# EndEffector-_Power.net
KiCad netlist of a schematic drawn in Altium Designer
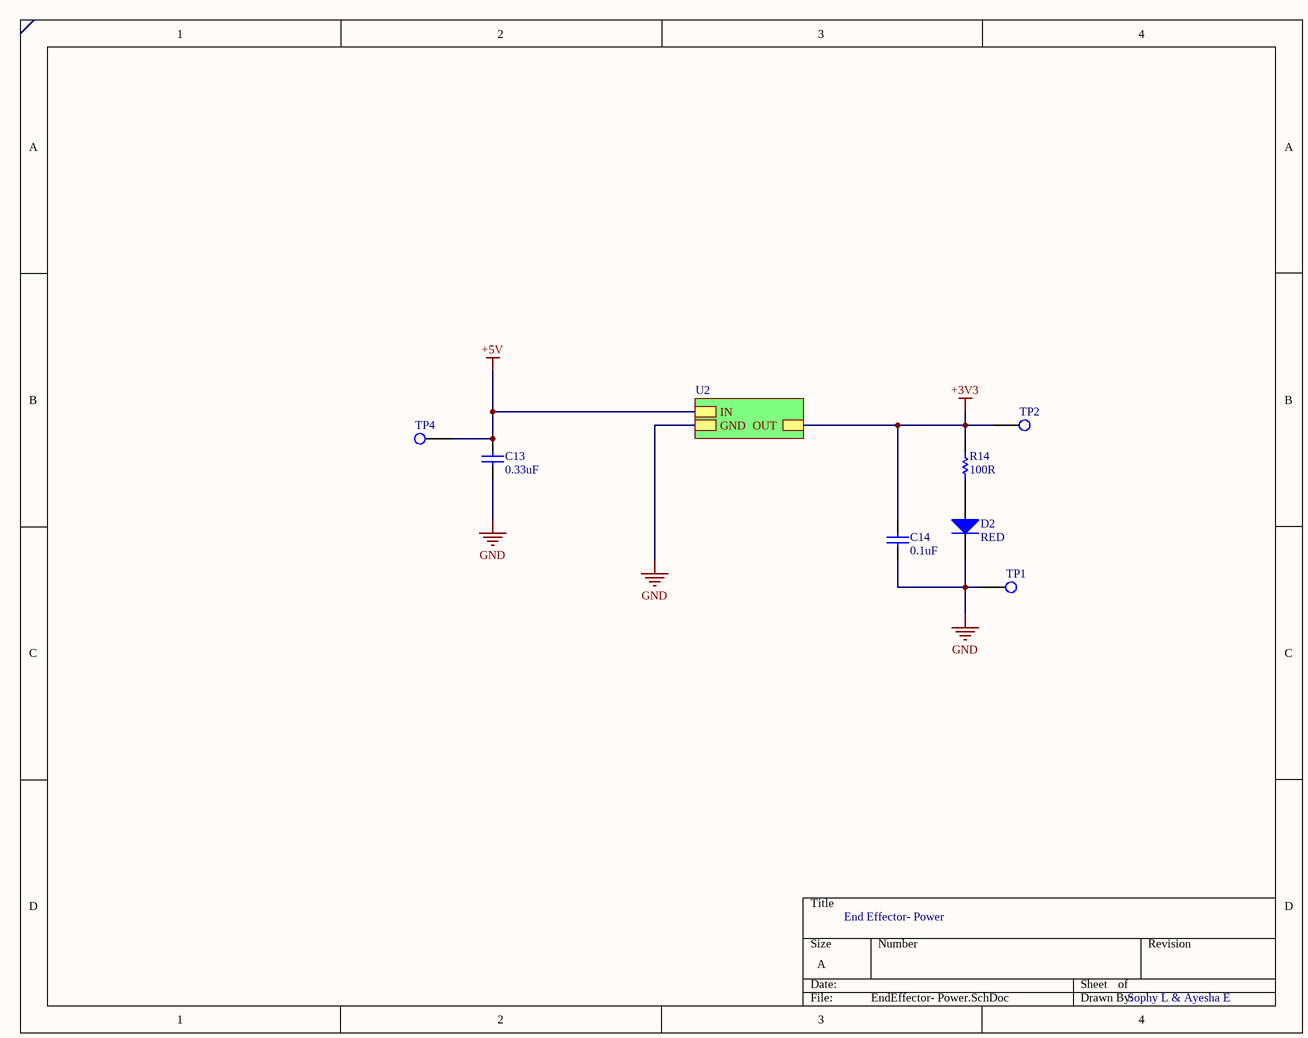
[diagram p0: EndEffector- Power.SchDoc]

(export (version "E")
  (design (tool "Eeschema 10.0.6"))
  (components
    (comp (ref "C13")
      (value "0.33uF")
      (footprint "CAPC0603(1608)55_N")
      (description "CAP CER 0.1UF 16V X7R 0603")
      (fields (field (name "PART NUMBER") "CC0603KRX7R7BB104") (field (name "MANUFACTURER") "Yageo"))
      (libsource (lib "UWRT_Schematic_Library_2019") (part "CAP_0.1uF_16V_0603"))
    )
    (comp (ref "C14")
      (value "0.1uF")
      (footprint "CAPC0603(1608)55_N")
      (description "CAP CER 0.1UF 16V X7R 0603")
      (fields (field (name "PART NUMBER") "CC0603KRX7R7BB104") (field (name "MANUFACTURER") "Yageo"))
      (libsource (lib "UWRT_Schematic_Library_2019") (part "CAP_0.1uF_16V_0603"))
    )
    (comp (ref "D2")
      (value "RED")
      (footprint "LED-1")
      (description "ESD PROTECTION DIODE")
      (fields (field (name "PART NUMBER") "BAS16GW") (field (name "MANUFACTURER") "Nexperia"))
      (libsource (lib "UWRT_Schematic_Library_2019") (part "DIO_BAS16GW"))
    )
    (comp (ref "R14")
      (value "100R")
      (footprint "RESC0201(0603)_N")
      (description "RES SMD 120 OHM 5% 1/10W 0603")
      (fields (field (name "MANUFACTURER") "Yageo") (field (name "TOLERANCE") "5%"))
      (libsource (lib "UWRT_Schematic_Library_2019") (part "RES_120R_0603"))
    )
    (comp (ref "TP1")
      (value "~")
      (footprint "TESTPOINT_LOOP")
      (libsource (lib "UWRT_Schematic_Library_2019") (part "TESTPOINT_LOOP"))
    )
    (comp (ref "TP2")
      (value "~")
      (footprint "TESTPOINT_LOOP")
      (libsource (lib "UWRT_Schematic_Library_2019") (part "TESTPOINT_LOOP"))
    )
    (comp (ref "TP4")
      (value "~")
      (footprint "TESTPOINT_LOOP")
      (libsource (lib "UWRT_Schematic_Library_2019") (part "TESTPOINT_LOOP"))
    )
  )
  (nets
    (net (code "1") (name "+3V3") (class "Default")
      (node (ref "C14") (pin "2") (pinfunction "2_2") (pintype "passive"))
      (node (ref "R14") (pin "2") (pinfunction "2_2") (pintype "passive"))
      (node (ref "TP2") (pin "1") (pinfunction "=value_1") (pintype "passive"))
    )
    (net (code "2") (name "+5V") (class "Default")
      (node (ref "C13") (pin "2") (pinfunction "2_2") (pintype "passive"))
      (node (ref "TP4") (pin "1") (pinfunction "=value_1") (pintype "passive"))
    )
    (net (code "3") (name "GND") (class "Default")
      (node (ref "C13") (pin "1") (pinfunction "1_1") (pintype "passive"))
      (node (ref "C14") (pin "1") (pinfunction "1_1") (pintype "passive"))
      (node (ref "D2") (pin "2") (pinfunction "K_2") (pintype "passive"))
      (node (ref "TP1") (pin "1") (pinfunction "=value_1") (pintype "passive"))
    )
    (net (code "4") (name "Net-(D2-A)") (class "Default")
      (node (ref "D2") (pin "1") (pinfunction "A_1") (pintype "passive"))
      (node (ref "R14") (pin "1") (pinfunction "1_1") (pintype "passive"))
    )
  )
)
